# newday_v0001.net
KiCad netlist of a schematic drawn in EAGLE
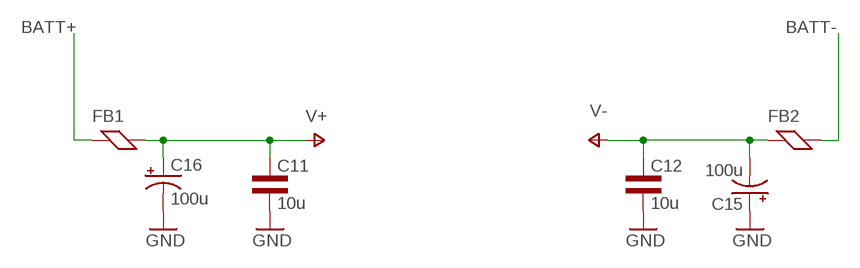
[diagram p0: schematic, sheet 1]
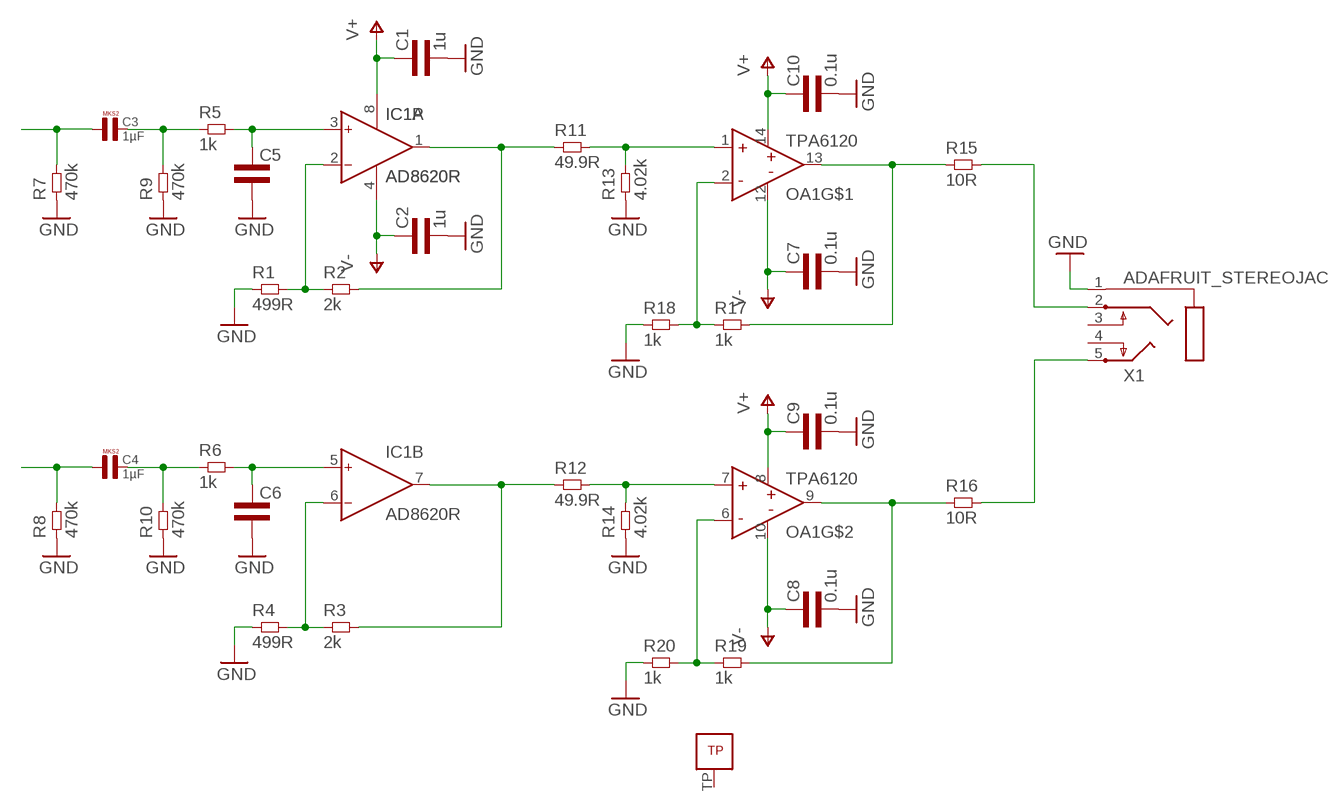
[diagram p1: schematic, sheet 2]

(export (version "E")
  (design (tool "Eeschema 10.0.6"))
  (components
    (comp (ref "C11")
      (value "10u")
      (footprint "eagle-import:1210L3")
      (libsource (lib "eagle-import") (part "CAP1210L3"))
    )
    (comp (ref "C12")
      (value "10u")
      (footprint "eagle-import:1210L3")
      (libsource (lib "eagle-import") (part "CAP1210L3"))
    )
    (comp (ref "C15")
      (value "100u")
      (footprint "eagle-import:E5-10,5")
      (libsource (lib "eagle-import") (part "CPOL-USE5-10.5"))
    )
    (comp (ref "C16")
      (value "100u")
      (footprint "eagle-import:E5-10,5")
      (libsource (lib "eagle-import") (part "CPOL-USE5-10.5"))
    )
    (comp (ref "FB1")
      (value "FERRITE0805L3")
      (footprint "eagle-import:0805L3")
      (libsource (lib "eagle-import") (part "FERRITE0805L3"))
    )
    (comp (ref "FB2")
      (value "FERRITE0805L3")
      (footprint "eagle-import:0805L3")
      (libsource (lib "eagle-import") (part "FERRITE0805L3"))
    )
    (comp (ref "C1")
      (value "1u")
      (footprint "eagle-import:0805L3")
      (libsource (lib "eagle-import") (part "CAP0805L3"))
    )
    (comp (ref "C2")
      (value "1u")
      (footprint "eagle-import:0805L3")
      (libsource (lib "eagle-import") (part "CAP0805L3"))
    )
    (comp (ref "C3")
      (value "1µF")
      (footprint "eagle-import:R5B3K5")
      (libsource (lib "eagle-import") (part "1µF"))
    )
    (comp (ref "C4")
      (value "1µF")
      (footprint "eagle-import:R5B3K5")
      (libsource (lib "eagle-import") (part "1µF"))
    )
    (comp (ref "C5")
      (value "CAP0603L3")
      (footprint "eagle-import:0603L3")
      (libsource (lib "eagle-import") (part "CAP0603L3"))
    )
    (comp (ref "C6")
      (value "CAP0603L3")
      (footprint "eagle-import:0603L3")
      (libsource (lib "eagle-import") (part "CAP0603L3"))
    )
    (comp (ref "C7")
      (value "0.1u")
      (footprint "eagle-import:0603L3")
      (libsource (lib "eagle-import") (part "CAP0603L3"))
    )
    (comp (ref "C8")
      (value "0.1u")
      (footprint "eagle-import:0603L3")
      (libsource (lib "eagle-import") (part "CAP0603L3"))
    )
    (comp (ref "C9")
      (value "0.1u")
      (footprint "eagle-import:0805L3")
      (libsource (lib "eagle-import") (part "CAP0805L3"))
    )
    (comp (ref "C10")
      (value "0.1u")
      (footprint "eagle-import:0805L3")
      (libsource (lib "eagle-import") (part "CAP0805L3"))
    )
    (comp (ref "IC1")
      (value "AD8620R")
      (footprint "eagle-import:SO8")
      (fields (field (name "MF") "ALTERA CORPORATION") (field (name "MPN") "AD8620ARZ"))
      (libsource (lib "eagle-import") (part "AD8620R"))
    )
    (comp (ref "OA1")
      (value "TPA6120QFN")
      (footprint "eagle-import:S-PVQFN-N14")
      (libsource (lib "eagle-import") (part "TPA6120QFN"))
    )
    (comp (ref "R1")
      (value "499R")
      (footprint "eagle-import:0603L3")
      (libsource (lib "eagle-import") (part "RES0603L3"))
    )
    (comp (ref "R2")
      (value "2k")
      (footprint "eagle-import:0603L3")
      (libsource (lib "eagle-import") (part "RES0603L3"))
    )
    (comp (ref "R3")
      (value "2k")
      (footprint "eagle-import:0603L3")
      (libsource (lib "eagle-import") (part "RES0603L3"))
    )
    (comp (ref "R4")
      (value "499R")
      (footprint "eagle-import:0603L3")
      (libsource (lib "eagle-import") (part "RES0603L3"))
    )
    (comp (ref "R5")
      (value "1k")
      (footprint "eagle-import:0603L3")
      (libsource (lib "eagle-import") (part "RES0603L3"))
    )
    (comp (ref "R6")
      (value "1k")
      (footprint "eagle-import:0603L3")
      (libsource (lib "eagle-import") (part "RES0603L3"))
    )
    (comp (ref "R7")
      (value "470k")
      (footprint "eagle-import:0603L3")
      (libsource (lib "eagle-import") (part "RES0603L3"))
    )
    (comp (ref "R8")
      (value "470k")
      (footprint "eagle-import:0603L3")
      (libsource (lib "eagle-import") (part "RES0603L3"))
    )
    (comp (ref "R9")
      (value "470k")
      (footprint "eagle-import:0603L3")
      (libsource (lib "eagle-import") (part "RES0603L3"))
    )
    (comp (ref "R10")
      (value "470k")
      (footprint "eagle-import:0603L3")
      (libsource (lib "eagle-import") (part "RES0603L3"))
    )
    (comp (ref "R11")
      (value "49.9R")
      (footprint "eagle-import:0805L3")
      (libsource (lib "eagle-import") (part "RES0805L3"))
    )
    (comp (ref "R12")
      (value "49.9R")
      (footprint "eagle-import:0805L3")
      (libsource (lib "eagle-import") (part "RES0805L3"))
    )
    (comp (ref "R13")
      (value "4.02k")
      (footprint "eagle-import:0805L3")
      (libsource (lib "eagle-import") (part "RES0805L3"))
    )
    (comp (ref "R14")
      (value "4.02k")
      (footprint "eagle-import:0805L3")
      (libsource (lib "eagle-import") (part "RES0805L3"))
    )
    (comp (ref "R15")
      (value "10R")
      (footprint "eagle-import:1210L3")
      (libsource (lib "eagle-import") (part "RES1210L3"))
    )
    (comp (ref "R16")
      (value "10R")
      (footprint "eagle-import:1210L3")
      (libsource (lib "eagle-import") (part "RES1210L3"))
    )
    (comp (ref "R17")
      (value "1k")
      (footprint "eagle-import:0603L3")
      (libsource (lib "eagle-import") (part "RES0603L3"))
    )
    (comp (ref "R18")
      (value "1k")
      (footprint "eagle-import:0603L3")
      (libsource (lib "eagle-import") (part "RES0603L3"))
    )
    (comp (ref "R19")
      (value "1k")
      (footprint "eagle-import:0603L3")
      (libsource (lib "eagle-import") (part "RES0603L3"))
    )
    (comp (ref "R20")
      (value "1k")
      (footprint "eagle-import:0603L3")
      (libsource (lib "eagle-import") (part "RES0603L3"))
    )
    (comp (ref "X1")
      (value "ADAFRUIT_STEREOJACK")
      (footprint "eagle-import:ADAFRUIT_STX3100")
      (libsource (lib "eagle-import") (part "ADAFRUIT_STEREOJACK"))
    )
  )
  (nets
    (net (code "1") (name "BATT+") (class "Default")
      (node (ref "FB1") (pin "1") (pinfunction "1_1") (pintype "bidirectional"))
    )
    (net (code "2") (name "BATT-") (class "Default")
      (node (ref "FB2") (pin "2") (pinfunction "2_2") (pintype "bidirectional"))
    )
    (net (code "3") (name "GND") (class "Default")
      (node (ref "C1") (pin "2") (pinfunction "2_2") (pintype "bidirectional"))
      (node (ref "C10") (pin "2") (pinfunction "2_2") (pintype "bidirectional"))
      (node (ref "C11") (pin "P$2") (pinfunction "2_P$2") (pintype "bidirectional"))
      (node (ref "C12") (pin "P$2") (pinfunction "2_P$2") (pintype "bidirectional"))
      (node (ref "C15") (pin "+") (pinfunction "+_+") (pintype "passive"))
      (node (ref "C16") (pin "-") (pinfunction "-_-") (pintype "passive"))
      (node (ref "C2") (pin "2") (pinfunction "2_2") (pintype "bidirectional"))
      (node (ref "C5") (pin "P$2") (pinfunction "2_P$2") (pintype "bidirectional"))
      (node (ref "C6") (pin "P$2") (pinfunction "2_P$2") (pintype "bidirectional"))
      (node (ref "C7") (pin "P$2") (pinfunction "2_P$2") (pintype "bidirectional"))
      (node (ref "C8") (pin "P$2") (pinfunction "2_P$2") (pintype "bidirectional"))
      (node (ref "C9") (pin "2") (pinfunction "2_2") (pintype "bidirectional"))
      (node (ref "R1") (pin "P$1") (pinfunction "1_P$1") (pintype "bidirectional"))
      (node (ref "R10") (pin "P$1") (pinfunction "1_P$1") (pintype "bidirectional"))
      (node (ref "R13") (pin "1") (pinfunction "1_1") (pintype "bidirectional"))
      (node (ref "R14") (pin "1") (pinfunction "1_1") (pintype "bidirectional"))
      (node (ref "R18") (pin "P$1") (pinfunction "1_P$1") (pintype "bidirectional"))
      (node (ref "R20") (pin "P$1") (pinfunction "1_P$1") (pintype "bidirectional"))
      (node (ref "R4") (pin "P$1") (pinfunction "1_P$1") (pintype "bidirectional"))
      (node (ref "R7") (pin "P$1") (pinfunction "1_P$1") (pintype "bidirectional"))
      (node (ref "R8") (pin "P$1") (pinfunction "1_P$1") (pintype "bidirectional"))
      (node (ref "R9") (pin "P$1") (pinfunction "1_P$1") (pintype "bidirectional"))
      (node (ref "X1") (pin "1") (pinfunction "1_1") (pintype "passive"))
    )
    (net (code "4") (name "Net-(C5-1)") (class "Default")
      (node (ref "C5") (pin "P$1") (pinfunction "1_P$1") (pintype "bidirectional"))
      (node (ref "IC1") (pin "3") (pinfunction "IN+_3") (pintype "input"))
      (node (ref "R5") (pin "P$2") (pinfunction "2_P$2") (pintype "bidirectional"))
    )
    (net (code "5") (name "Net-(C6-1)") (class "Default")
      (node (ref "C6") (pin "P$1") (pinfunction "1_P$1") (pintype "bidirectional"))
      (node (ref "IC1") (pin "5") (pinfunction "IN+_5") (pintype "input"))
      (node (ref "R6") (pin "P$2") (pinfunction "2_P$2") (pintype "bidirectional"))
    )
    (net (code "6") (name "Net-(IC1A-IN-)") (class "Default")
      (node (ref "IC1") (pin "2") (pinfunction "IN-_2") (pintype "input"))
      (node (ref "R1") (pin "P$2") (pinfunction "2_P$2") (pintype "bidirectional"))
      (node (ref "R2") (pin "P$1") (pinfunction "1_P$1") (pintype "bidirectional"))
    )
    (net (code "7") (name "Net-(IC1A-OUT)") (class "Default")
      (node (ref "IC1") (pin "1") (pinfunction "OUT_1") (pintype "output"))
      (node (ref "R11") (pin "1") (pinfunction "1_1") (pintype "bidirectional"))
      (node (ref "R2") (pin "P$2") (pinfunction "2_P$2") (pintype "bidirectional"))
    )
    (net (code "8") (name "Net-(IC1B-IN-)") (class "Default")
      (node (ref "IC1") (pin "6") (pinfunction "IN-_6") (pintype "input"))
      (node (ref "R3") (pin "P$1") (pinfunction "1_P$1") (pintype "bidirectional"))
      (node (ref "R4") (pin "P$2") (pinfunction "2_P$2") (pintype "bidirectional"))
    )
    (net (code "9") (name "Net-(IC1B-OUT)") (class "Default")
      (node (ref "IC1") (pin "7") (pinfunction "OUT_7") (pintype "output"))
      (node (ref "R12") (pin "1") (pinfunction "1_1") (pintype "bidirectional"))
      (node (ref "R3") (pin "P$2") (pinfunction "2_P$2") (pintype "bidirectional"))
    )
    (net (code "10") (name "Net-(OA1A-IN+)") (class "Default")
      (node (ref "OA1") (pin "1") (pinfunction "IN+_1") (pintype "bidirectional"))
      (node (ref "R11") (pin "2") (pinfunction "2_2") (pintype "bidirectional"))
      (node (ref "R13") (pin "2") (pinfunction "2_2") (pintype "bidirectional"))
    )
    (net (code "11") (name "Net-(OA1A-IN-)") (class "Default")
      (node (ref "OA1") (pin "2") (pinfunction "IN-_2") (pintype "bidirectional"))
      (node (ref "R17") (pin "P$1") (pinfunction "1_P$1") (pintype "bidirectional"))
      (node (ref "R18") (pin "P$2") (pinfunction "2_P$2") (pintype "bidirectional"))
    )
    (net (code "12") (name "Net-(OA1A-OUT)") (class "Default")
      (node (ref "OA1") (pin "13") (pinfunction "OUT_13") (pintype "bidirectional"))
      (node (ref "R15") (pin "P$1") (pinfunction "1_P$1") (pintype "bidirectional"))
      (node (ref "R17") (pin "P$2") (pinfunction "2_P$2") (pintype "bidirectional"))
    )
    (net (code "13") (name "Net-(OA1B-IN+)") (class "Default")
      (node (ref "OA1") (pin "7") (pinfunction "IN+_7") (pintype "bidirectional"))
      (node (ref "R12") (pin "2") (pinfunction "2_2") (pintype "bidirectional"))
      (node (ref "R14") (pin "2") (pinfunction "2_2") (pintype "bidirectional"))
    )
    (net (code "14") (name "Net-(OA1B-IN-)") (class "Default")
      (node (ref "OA1") (pin "6") (pinfunction "IN-_6") (pintype "bidirectional"))
      (node (ref "R19") (pin "P$1") (pinfunction "1_P$1") (pintype "bidirectional"))
      (node (ref "R20") (pin "P$2") (pinfunction "2_P$2") (pintype "bidirectional"))
    )
    (net (code "15") (name "Net-(OA1B-OUT)") (class "Default")
      (node (ref "OA1") (pin "9") (pinfunction "OUT_9") (pintype "bidirectional"))
      (node (ref "R16") (pin "P$1") (pinfunction "1_P$1") (pintype "bidirectional"))
      (node (ref "R19") (pin "P$2") (pinfunction "2_P$2") (pintype "bidirectional"))
    )
    (net (code "16") (name "Net-(R5-1)") (class "Default")
      (node (ref "C3") (pin "2") (pinfunction "2_2") (pintype "passive"))
      (node (ref "R5") (pin "P$1") (pinfunction "1_P$1") (pintype "bidirectional"))
      (node (ref "R9") (pin "P$2") (pinfunction "2_P$2") (pintype "bidirectional"))
    )
    (net (code "17") (name "Net-(R7-2)") (class "Default")
      (node (ref "C3") (pin "1") (pinfunction "1_1") (pintype "passive"))
      (node (ref "R7") (pin "P$2") (pinfunction "2_P$2") (pintype "bidirectional"))
    )
    (net (code "18") (name "Net-(R8-2)") (class "Default")
      (node (ref "C4") (pin "1") (pinfunction "1_1") (pintype "passive"))
      (node (ref "R8") (pin "P$2") (pinfunction "2_P$2") (pintype "bidirectional"))
    )
    (net (code "19") (name "Net-(R10-2)") (class "Default")
      (node (ref "C4") (pin "2") (pinfunction "2_2") (pintype "passive"))
      (node (ref "R10") (pin "P$2") (pinfunction "2_P$2") (pintype "bidirectional"))
      (node (ref "R6") (pin "P$1") (pinfunction "1_P$1") (pintype "bidirectional"))
    )
    (net (code "20") (name "Net-(R15-2)") (class "Default")
      (node (ref "R15") (pin "P$2") (pinfunction "2_P$2") (pintype "bidirectional"))
      (node (ref "X1") (pin "2") (pinfunction "2_2") (pintype "passive"))
    )
    (net (code "21") (name "Net-(R16-2)") (class "Default")
      (node (ref "R16") (pin "P$2") (pinfunction "2_P$2") (pintype "bidirectional"))
      (node (ref "X1") (pin "5") (pinfunction "5_5") (pintype "passive"))
    )
    (net (code "22") (name "V+") (class "Default")
      (node (ref "C1") (pin "1") (pinfunction "1_1") (pintype "bidirectional"))
      (node (ref "C10") (pin "1") (pinfunction "1_1") (pintype "bidirectional"))
      (node (ref "C11") (pin "P$1") (pinfunction "1_P$1") (pintype "bidirectional"))
      (node (ref "C16") (pin "+") (pinfunction "+_+") (pintype "passive"))
      (node (ref "C9") (pin "1") (pinfunction "1_1") (pintype "bidirectional"))
      (node (ref "FB1") (pin "2") (pinfunction "2_2") (pintype "bidirectional"))
      (node (ref "IC1") (pin "8") (pinfunction "V+_8") (pintype "power_in"))
      (node (ref "OA1") (pin "14") (pinfunction "V+_14") (pintype "bidirectional"))
      (node (ref "OA1") (pin "8") (pinfunction "V+_8") (pintype "bidirectional"))
    )
    (net (code "23") (name "V-") (class "Default")
      (node (ref "C12") (pin "P$1") (pinfunction "1_P$1") (pintype "bidirectional"))
      (node (ref "C15") (pin "-") (pinfunction "-_-") (pintype "passive"))
      (node (ref "C2") (pin "1") (pinfunction "1_1") (pintype "bidirectional"))
      (node (ref "C7") (pin "P$1") (pinfunction "1_P$1") (pintype "bidirectional"))
      (node (ref "C8") (pin "P$1") (pinfunction "1_P$1") (pintype "bidirectional"))
      (node (ref "FB2") (pin "1") (pinfunction "1_1") (pintype "bidirectional"))
      (node (ref "IC1") (pin "4") (pinfunction "V-_4") (pintype "power_in"))
      (node (ref "OA1") (pin "10") (pinfunction "V-_10") (pintype "bidirectional"))
      (node (ref "OA1") (pin "12") (pinfunction "V-_12") (pintype "bidirectional"))
    )
    (net (code "24") (name "unconnected-(OA1-PadTP)") (class "Default")
      (node (ref "OA1") (pin "TP") (pinfunction "TP_TP") (pintype "bidirectional"))
    )
    (net (code "25") (name "unconnected-(X1-Pad3)") (class "Default")
      (node (ref "X1") (pin "3") (pinfunction "3_3") (pintype "passive"))
    )
    (net (code "26") (name "unconnected-(X1-Pad4)") (class "Default")
      (node (ref "X1") (pin "4") (pinfunction "4_4") (pintype "passive"))
    )
  )
)
